# H_M_CD.net
KiCad netlist of a schematic drawn in EAGLE
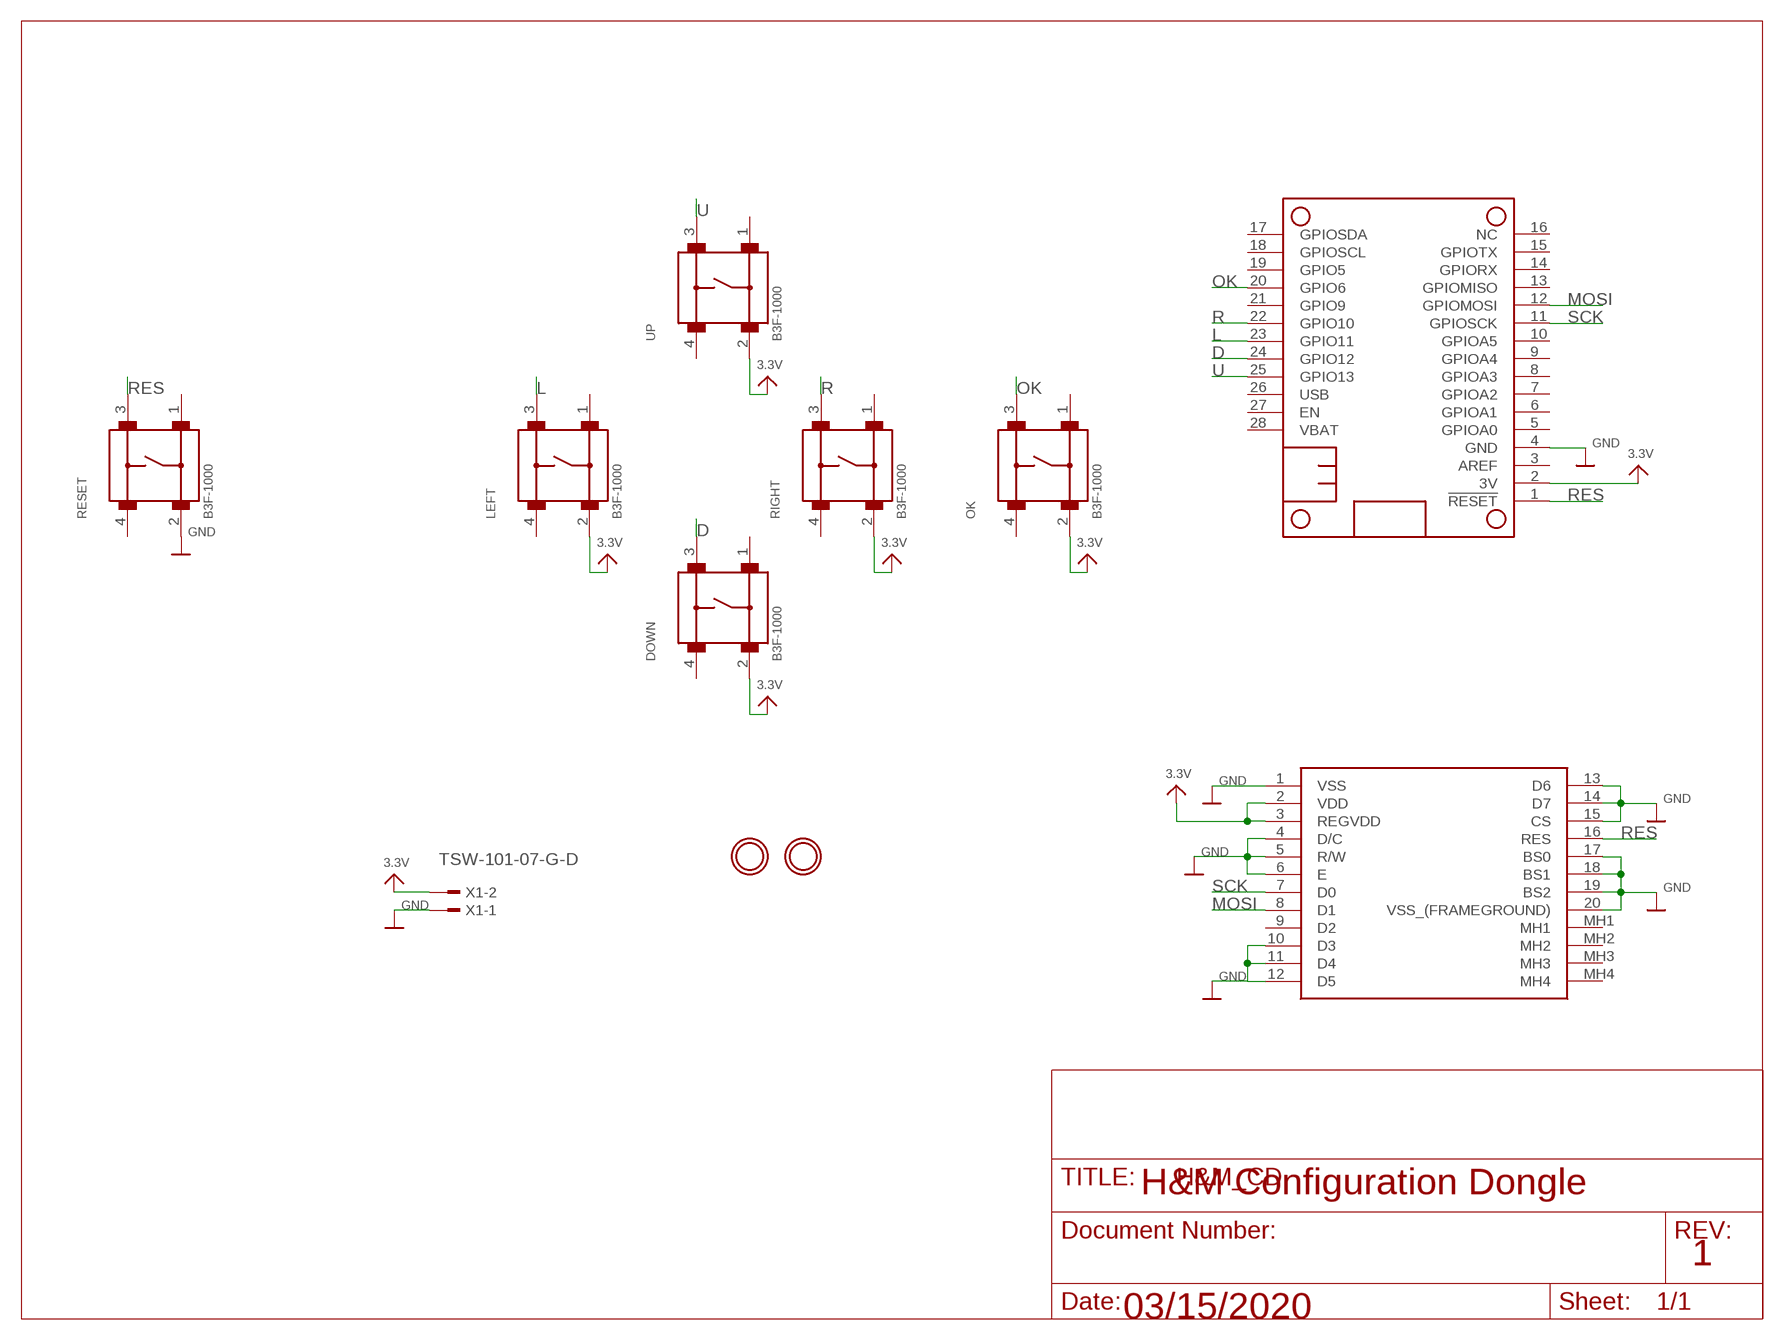
[diagram p0: schematic, sheet 1]

(export (version "E")
  (design (tool "Eeschema 10.0.6"))
  (components
    (comp (ref "20X4OLED")
      (value "NHD-0420CW-AW3")
      (footprint "eagle-import:NHD0420CWAW3")
      (fields (field (name "MOUSER_PART_NUMBER") "763-NHD-0420CW-AW3"))
      (libsource (lib "eagle-import") (part "NHD-0420CW-AW3"))
    )
    (comp (ref "ATSAMD21M0")
      (value "FEATHERWING_NODIM")
      (footprint "eagle-import:FEATHERWING_DIM")
      (libsource (lib "eagle-import") (part "FEATHERWING_NODIM"))
    )
    (comp (ref "DOWN")
      (value "B3F-1000")
      (footprint "eagle-import:B3F-1000")
      (fields
        (field (name "DIGI_KEY_PART_NUMBER") "SW400-ND")
        (field (name "MANUFACTURER") "Omron Electronics Inc-EMC Div")
        (field (name "CREATED_BY") "PCBLayout.com")
      )
      (libsource (lib "eagle-import") (part "B3F-1000"))
    )
    (comp (ref "LEFT")
      (value "B3F-1000")
      (footprint "eagle-import:B3F-1000")
      (fields
        (field (name "DIGI_KEY_PART_NUMBER") "SW400-ND")
        (field (name "MANUFACTURER") "Omron Electronics Inc-EMC Div")
        (field (name "CREATED_BY") "PCBLayout.com")
      )
      (libsource (lib "eagle-import") (part "B3F-1000"))
    )
    (comp (ref "OK")
      (value "B3F-1000")
      (footprint "eagle-import:B3F-1000")
      (fields
        (field (name "DIGI_KEY_PART_NUMBER") "SW400-ND")
        (field (name "MANUFACTURER") "Omron Electronics Inc-EMC Div")
        (field (name "CREATED_BY") "PCBLayout.com")
      )
      (libsource (lib "eagle-import") (part "B3F-1000"))
    )
    (comp (ref "RESET")
      (value "B3F-1000")
      (footprint "eagle-import:B3F-1000")
      (fields
        (field (name "DIGI_KEY_PART_NUMBER") "SW400-ND")
        (field (name "MANUFACTURER") "Omron Electronics Inc-EMC Div")
        (field (name "CREATED_BY") "PCBLayout.com")
      )
      (libsource (lib "eagle-import") (part "B3F-1000"))
    )
    (comp (ref "RIGHT")
      (value "B3F-1000")
      (footprint "eagle-import:B3F-1000")
      (fields
        (field (name "DIGI_KEY_PART_NUMBER") "SW400-ND")
        (field (name "MANUFACTURER") "Omron Electronics Inc-EMC Div")
        (field (name "CREATED_BY") "PCBLayout.com")
      )
      (libsource (lib "eagle-import") (part "B3F-1000"))
    )
    (comp (ref "U$15")
      (value "MOUNTINGHOLE2.5")
      (footprint "eagle-import:MOUNTINGHOLE_2.5_PLATED")
      (libsource (lib "eagle-import") (part "MOUNTINGHOLE2.5"))
    )
    (comp (ref "U$16")
      (value "MOUNTINGHOLE2.5")
      (footprint "eagle-import:MOUNTINGHOLE_2.5_PLATED")
      (libsource (lib "eagle-import") (part "MOUNTINGHOLE2.5"))
    )
    (comp (ref "UP")
      (value "B3F-1000")
      (footprint "eagle-import:B3F-1000")
      (fields
        (field (name "DIGI_KEY_PART_NUMBER") "SW400-ND")
        (field (name "MANUFACTURER") "Omron Electronics Inc-EMC Div")
        (field (name "CREATED_BY") "PCBLayout.com")
      )
      (libsource (lib "eagle-import") (part "B3F-1000"))
    )
    (comp (ref "X1")
      (value "TSW-101-07-G-D")
      (footprint "eagle-import:TSW-101-XX-G-D")
      (fields (field (name "MF") "Samtec Inc."))
      (libsource (lib "eagle-import") (part "TSW-101--G-D07"))
    )
  )
  (nets
    (net (code "1") (name "/D") (class "Default")
      (node (ref "ATSAMD21M0") (pin "24") (pinfunction "GPIO12_24") (pintype "bidirectional"))
      (node (ref "DOWN") (pin "3") (pinfunction "3_3") (pintype "passive"))
    )
    (net (code "2") (name "/L") (class "Default")
      (node (ref "ATSAMD21M0") (pin "23") (pinfunction "GPIO11_23") (pintype "bidirectional"))
      (node (ref "LEFT") (pin "3") (pinfunction "3_3") (pintype "passive"))
    )
    (net (code "3") (name "/MOSI") (class "Default")
      (node (ref "20X4OLED") (pin "8") (pinfunction "D1_8") (pintype "bidirectional"))
      (node (ref "ATSAMD21M0") (pin "12") (pinfunction "GPIOMOSI_12") (pintype "bidirectional"))
    )
    (net (code "4") (name "/OK") (class "Default")
      (node (ref "ATSAMD21M0") (pin "20") (pinfunction "GPIO6_20") (pintype "bidirectional"))
      (node (ref "OK") (pin "3") (pinfunction "3_3") (pintype "passive"))
    )
    (net (code "5") (name "/R") (class "Default")
      (node (ref "ATSAMD21M0") (pin "22") (pinfunction "GPIO10_22") (pintype "bidirectional"))
      (node (ref "RIGHT") (pin "3") (pinfunction "3_3") (pintype "passive"))
    )
    (net (code "6") (name "/RES") (class "Default")
      (node (ref "20X4OLED") (pin "16") (pinfunction "RES_16") (pintype "bidirectional"))
      (node (ref "ATSAMD21M0") (pin "1") (pinfunction "~{RESET}_1") (pintype "input"))
      (node (ref "RESET") (pin "3") (pinfunction "3_3") (pintype "passive"))
    )
    (net (code "7") (name "/SCK") (class "Default")
      (node (ref "20X4OLED") (pin "7") (pinfunction "D0_7") (pintype "bidirectional"))
      (node (ref "ATSAMD21M0") (pin "11") (pinfunction "GPIOSCK_11") (pintype "bidirectional"))
    )
    (net (code "8") (name "/U") (class "Default")
      (node (ref "ATSAMD21M0") (pin "25") (pinfunction "GPIO13_25") (pintype "bidirectional"))
      (node (ref "UP") (pin "3") (pinfunction "3_3") (pintype "passive"))
    )
    (net (code "9") (name "/USB") (class "Default")
      (node (ref "ATSAMD21M0") (pin "26") (pinfunction "USB_26") (pintype "power_in"))
    )
    (net (code "10") (name "/VBAT") (class "Default")
      (node (ref "ATSAMD21M0") (pin "28") (pinfunction "VBAT_28") (pintype "power_in"))
    )
    (net (code "11") (name "3.3V") (class "Default")
      (node (ref "20X4OLED") (pin "2") (pinfunction "VDD_2") (pintype "bidirectional"))
      (node (ref "20X4OLED") (pin "3") (pinfunction "REGVDD_3") (pintype "bidirectional"))
      (node (ref "ATSAMD21M0") (pin "2") (pinfunction "3V_2") (pintype "power_in"))
      (node (ref "DOWN") (pin "2") (pinfunction "2_2") (pintype "passive"))
      (node (ref "LEFT") (pin "2") (pinfunction "2_2") (pintype "passive"))
      (node (ref "OK") (pin "2") (pinfunction "2_2") (pintype "passive"))
      (node (ref "RIGHT") (pin "2") (pinfunction "2_2") (pintype "passive"))
      (node (ref "UP") (pin "2") (pinfunction "2_2") (pintype "passive"))
      (node (ref "X1") (pin "2") (pinfunction "1_2") (pintype "passive"))
    )
    (net (code "12") (name "GND") (class "Default")
      (node (ref "20X4OLED") (pin "1") (pinfunction "VSS_1") (pintype "bidirectional"))
      (node (ref "20X4OLED") (pin "10") (pinfunction "D3_10") (pintype "bidirectional"))
      (node (ref "20X4OLED") (pin "11") (pinfunction "D4_11") (pintype "bidirectional"))
      (node (ref "20X4OLED") (pin "12") (pinfunction "D5_12") (pintype "bidirectional"))
      (node (ref "20X4OLED") (pin "13") (pinfunction "D6_13") (pintype "bidirectional"))
      (node (ref "20X4OLED") (pin "14") (pinfunction "D7_14") (pintype "bidirectional"))
      (node (ref "20X4OLED") (pin "15") (pinfunction "CS_15") (pintype "bidirectional"))
      (node (ref "20X4OLED") (pin "17") (pinfunction "BS0_17") (pintype "bidirectional"))
      (node (ref "20X4OLED") (pin "18") (pinfunction "BS1_18") (pintype "bidirectional"))
      (node (ref "20X4OLED") (pin "19") (pinfunction "BS2_19") (pintype "bidirectional"))
      (node (ref "20X4OLED") (pin "20") (pinfunction "VSS_(FRAMEGROUND)_20") (pintype "bidirectional"))
      (node (ref "20X4OLED") (pin "4") (pinfunction "D/C_4") (pintype "bidirectional"))
      (node (ref "20X4OLED") (pin "5") (pinfunction "R/W_5") (pintype "bidirectional"))
      (node (ref "20X4OLED") (pin "6") (pinfunction "E_6") (pintype "bidirectional"))
      (node (ref "ATSAMD21M0") (pin "4") (pinfunction "GND_4") (pintype "power_in"))
      (node (ref "RESET") (pin "2") (pinfunction "2_2") (pintype "passive"))
      (node (ref "X1") (pin "1") (pinfunction "1_1") (pintype "passive"))
    )
    (net (code "13") (name "unconnected-(20X4OLED-D2-Pad9)") (class "Default")
      (node (ref "20X4OLED") (pin "9") (pinfunction "D2_9") (pintype "bidirectional"))
    )
    (net (code "14") (name "unconnected-(20X4OLED-PadMH1)") (class "Default")
      (node (ref "20X4OLED") (pin "MH1") (pinfunction "MH1_MH1") (pintype "bidirectional"))
    )
    (net (code "15") (name "unconnected-(20X4OLED-PadMH2)") (class "Default")
      (node (ref "20X4OLED") (pin "MH2") (pinfunction "MH2_MH2") (pintype "bidirectional"))
    )
    (net (code "16") (name "unconnected-(20X4OLED-PadMH3)") (class "Default")
      (node (ref "20X4OLED") (pin "MH3") (pinfunction "MH3_MH3") (pintype "bidirectional"))
    )
    (net (code "17") (name "unconnected-(20X4OLED-PadMH4)") (class "Default")
      (node (ref "20X4OLED") (pin "MH4") (pinfunction "MH4_MH4") (pintype "bidirectional"))
    )
    (net (code "18") (name "unconnected-(ATSAMD21M0-AREF-Pad3)") (class "Default")
      (node (ref "ATSAMD21M0") (pin "3") (pinfunction "AREF_3") (pintype "passive"))
    )
    (net (code "19") (name "unconnected-(ATSAMD21M0-EN-Pad27)") (class "Default")
      (node (ref "ATSAMD21M0") (pin "27") (pinfunction "EN_27") (pintype "passive"))
    )
    (net (code "20") (name "unconnected-(ATSAMD21M0-GPIO5-Pad19)") (class "Default")
      (node (ref "ATSAMD21M0") (pin "19") (pinfunction "GPIO5_19") (pintype "bidirectional"))
    )
    (net (code "21") (name "unconnected-(ATSAMD21M0-GPIO9-Pad21)") (class "Default")
      (node (ref "ATSAMD21M0") (pin "21") (pinfunction "GPIO9_21") (pintype "bidirectional"))
    )
    (net (code "22") (name "unconnected-(ATSAMD21M0-GPIOA0-Pad5)") (class "Default")
      (node (ref "ATSAMD21M0") (pin "5") (pinfunction "GPIOA0_5") (pintype "bidirectional"))
    )
    (net (code "23") (name "unconnected-(ATSAMD21M0-GPIOA1-Pad6)") (class "Default")
      (node (ref "ATSAMD21M0") (pin "6") (pinfunction "GPIOA1_6") (pintype "bidirectional"))
    )
    (net (code "24") (name "unconnected-(ATSAMD21M0-GPIOA2-Pad7)") (class "Default")
      (node (ref "ATSAMD21M0") (pin "7") (pinfunction "GPIOA2_7") (pintype "bidirectional"))
    )
    (net (code "25") (name "unconnected-(ATSAMD21M0-GPIOA3-Pad8)") (class "Default")
      (node (ref "ATSAMD21M0") (pin "8") (pinfunction "GPIOA3_8") (pintype "bidirectional"))
    )
    (net (code "26") (name "unconnected-(ATSAMD21M0-GPIOA4-Pad9)") (class "Default")
      (node (ref "ATSAMD21M0") (pin "9") (pinfunction "GPIOA4_9") (pintype "bidirectional"))
    )
    (net (code "27") (name "unconnected-(ATSAMD21M0-GPIOA5-Pad10)") (class "Default")
      (node (ref "ATSAMD21M0") (pin "10") (pinfunction "GPIOA5_10") (pintype "bidirectional"))
    )
    (net (code "28") (name "unconnected-(ATSAMD21M0-GPIOMISO-Pad13)") (class "Default")
      (node (ref "ATSAMD21M0") (pin "13") (pinfunction "GPIOMISO_13") (pintype "bidirectional"))
    )
    (net (code "29") (name "unconnected-(ATSAMD21M0-GPIORX-Pad14)") (class "Default")
      (node (ref "ATSAMD21M0") (pin "14") (pinfunction "GPIORX_14") (pintype "bidirectional"))
    )
    (net (code "30") (name "unconnected-(ATSAMD21M0-GPIOSCL-Pad18)") (class "Default")
      (node (ref "ATSAMD21M0") (pin "18") (pinfunction "GPIOSCL_18") (pintype "bidirectional"))
    )
    (net (code "31") (name "unconnected-(ATSAMD21M0-GPIOSDA-Pad17)") (class "Default")
      (node (ref "ATSAMD21M0") (pin "17") (pinfunction "GPIOSDA_17") (pintype "bidirectional"))
    )
    (net (code "32") (name "unconnected-(ATSAMD21M0-GPIOTX-Pad15)") (class "Default")
      (node (ref "ATSAMD21M0") (pin "15") (pinfunction "GPIOTX_15") (pintype "bidirectional"))
    )
    (net (code "33") (name "unconnected-(ATSAMD21M0-NC-Pad16)") (class "Default")
      (node (ref "ATSAMD21M0") (pin "16") (pinfunction "NC_16") (pintype "passive"))
    )
    (net (code "34") (name "unconnected-(DOWN-Pad1)") (class "Default")
      (node (ref "DOWN") (pin "1") (pinfunction "1_1") (pintype "passive"))
    )
    (net (code "35") (name "unconnected-(DOWN-Pad4)") (class "Default")
      (node (ref "DOWN") (pin "4") (pinfunction "4_4") (pintype "passive"))
    )
    (net (code "36") (name "unconnected-(LEFT-Pad1)") (class "Default")
      (node (ref "LEFT") (pin "1") (pinfunction "1_1") (pintype "passive"))
    )
    (net (code "37") (name "unconnected-(LEFT-Pad4)") (class "Default")
      (node (ref "LEFT") (pin "4") (pinfunction "4_4") (pintype "passive"))
    )
    (net (code "38") (name "unconnected-(OK-Pad1)") (class "Default")
      (node (ref "OK") (pin "1") (pinfunction "1_1") (pintype "passive"))
    )
    (net (code "39") (name "unconnected-(OK-Pad4)") (class "Default")
      (node (ref "OK") (pin "4") (pinfunction "4_4") (pintype "passive"))
    )
    (net (code "40") (name "unconnected-(RESET-Pad1)") (class "Default")
      (node (ref "RESET") (pin "1") (pinfunction "1_1") (pintype "passive"))
    )
    (net (code "41") (name "unconnected-(RESET-Pad4)") (class "Default")
      (node (ref "RESET") (pin "4") (pinfunction "4_4") (pintype "passive"))
    )
    (net (code "42") (name "unconnected-(RIGHT-Pad1)") (class "Default")
      (node (ref "RIGHT") (pin "1") (pinfunction "1_1") (pintype "passive"))
    )
    (net (code "43") (name "unconnected-(RIGHT-Pad4)") (class "Default")
      (node (ref "RIGHT") (pin "4") (pinfunction "4_4") (pintype "passive"))
    )
    (net (code "44") (name "unconnected-(UP-Pad1)") (class "Default")
      (node (ref "UP") (pin "1") (pinfunction "1_1") (pintype "passive"))
    )
    (net (code "45") (name "unconnected-(UP-Pad4)") (class "Default")
      (node (ref "UP") (pin "4") (pinfunction "4_4") (pintype "passive"))
    )
  )
)
